# MotorShieldTestbench_ro.net
KiCad netlist of a schematic drawn in EAGLE
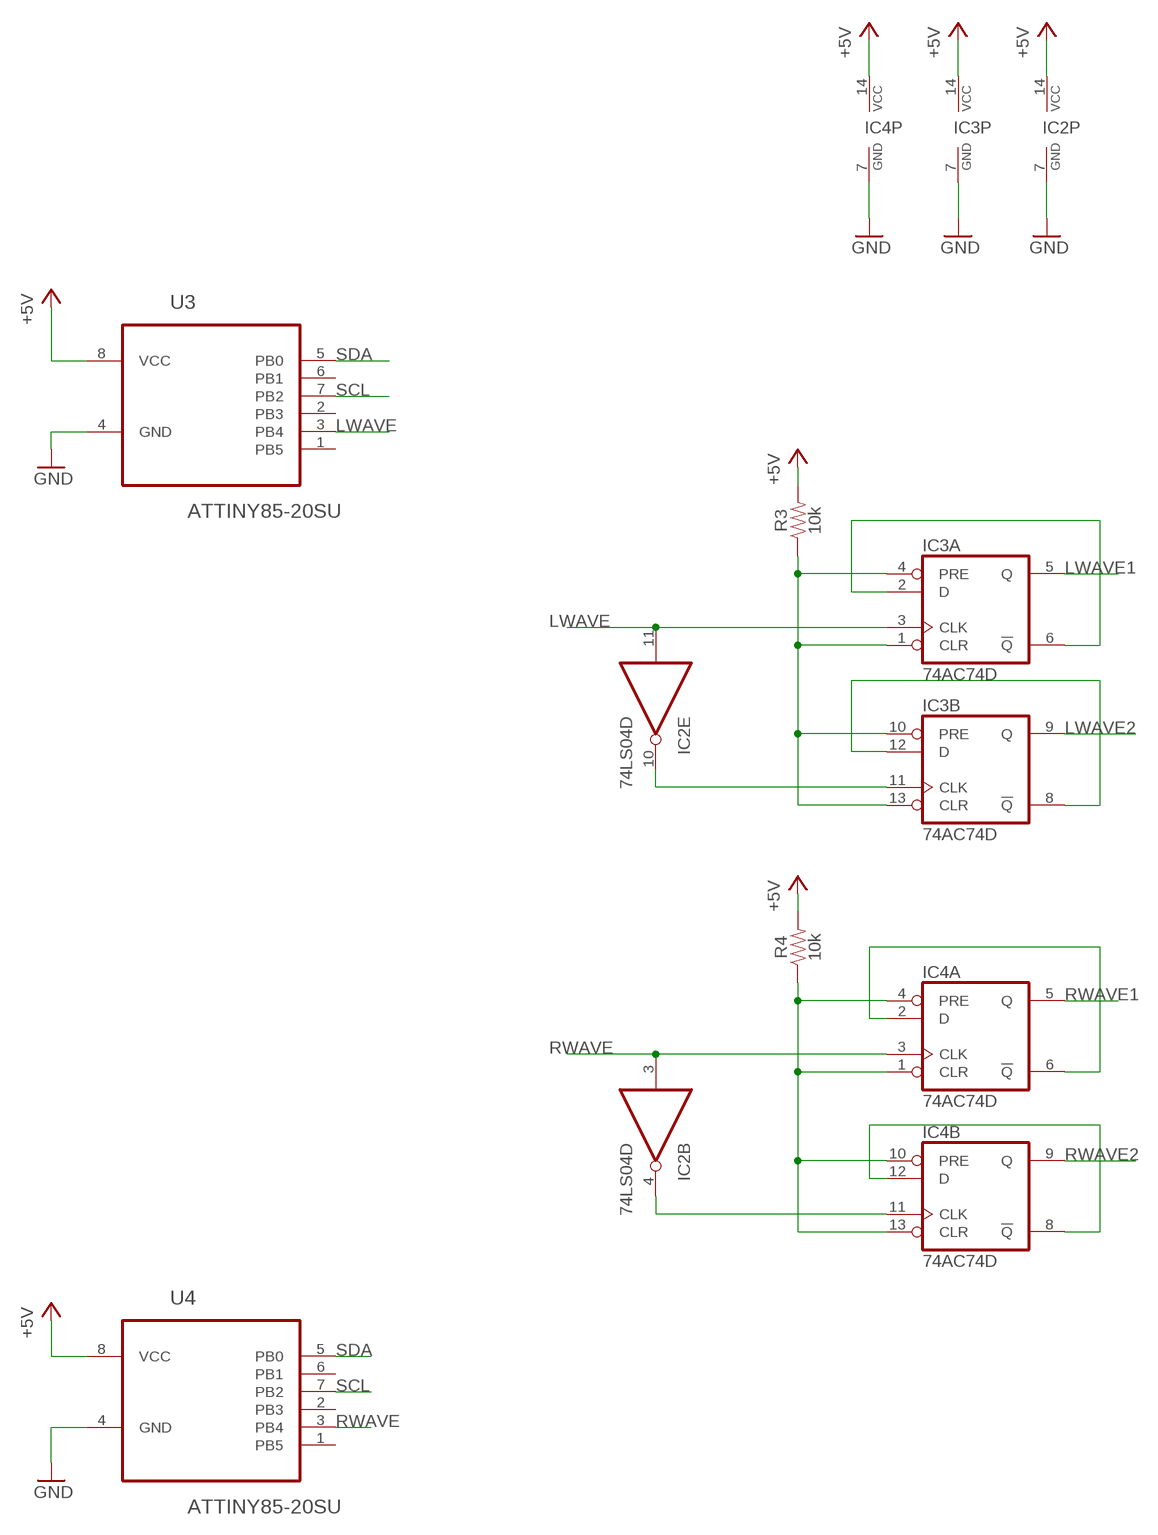
[diagram p0: schematic, sheet 1, part 1 of 2]
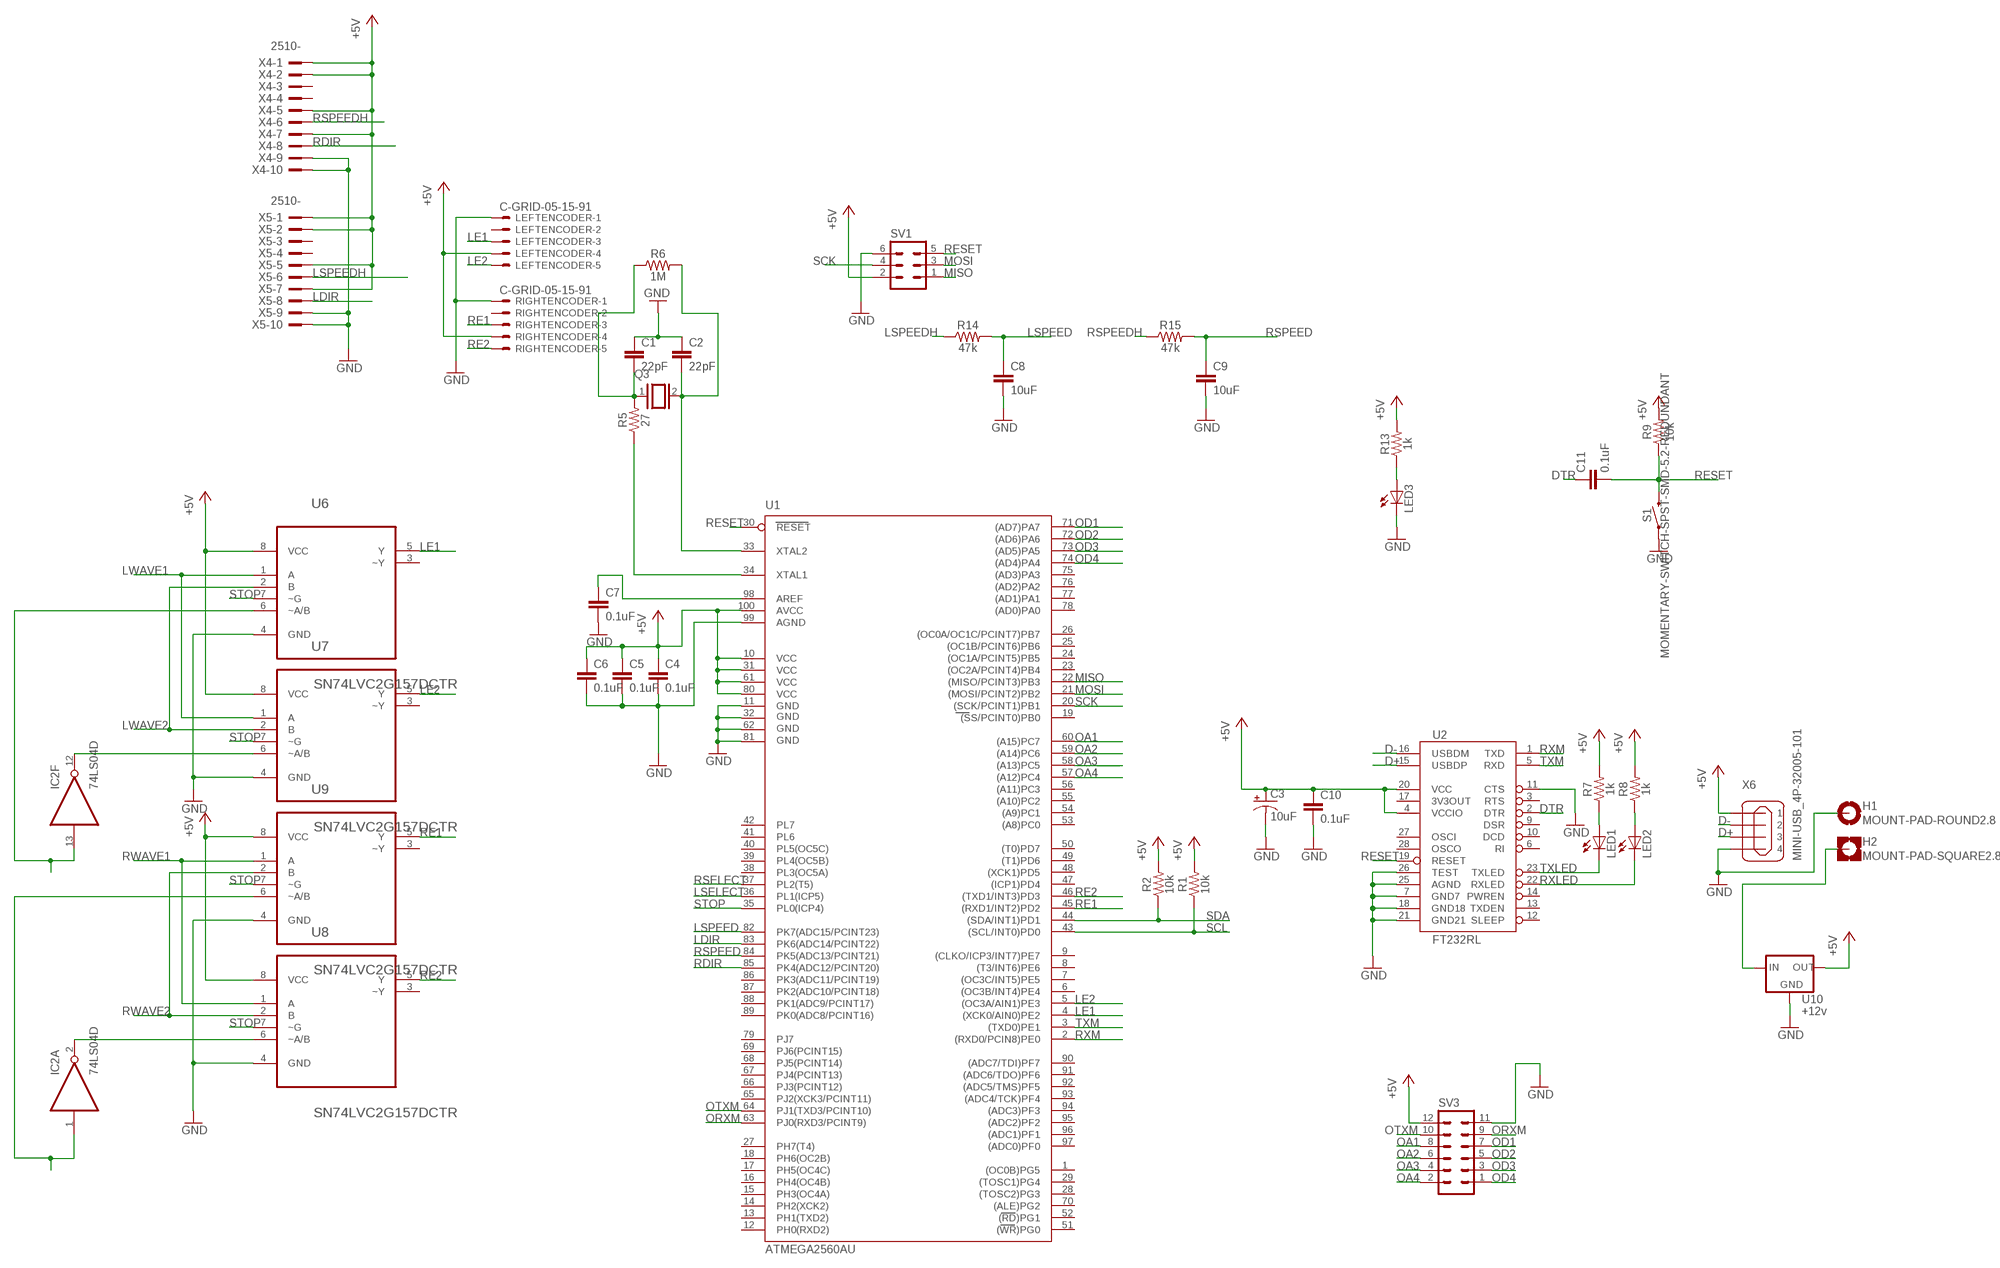
[diagram p1: schematic, sheet 1, part 2 of 2]

(export (version "E")
  (design (tool "Eeschema 10.0.6"))
  (components
    (comp (ref "C1")
      (value "22pF")
      (footprint "eagle-import:0603")
      (libsource (lib "eagle-import") (part "22PF-0603-50V-5%"))
    )
    (comp (ref "C2")
      (value "22pF")
      (footprint "eagle-import:0603")
      (libsource (lib "eagle-import") (part "22PF-0603-50V-5%"))
    )
    (comp (ref "C3")
      (value "10uF")
      (footprint "eagle-import:0603-POLAR")
      (libsource (lib "eagle-import") (part "10UF-POLAR-0603-6.3V-20%(TANT)"))
    )
    (comp (ref "C4")
      (value "0.1uF")
      (footprint "eagle-import:0603")
      (libsource (lib "eagle-import") (part "0.1UF-0603-25V-(+80/-20%)"))
    )
    (comp (ref "C5")
      (value "0.1uF")
      (footprint "eagle-import:0603")
      (libsource (lib "eagle-import") (part "0.1UF-0603-25V-(+80/-20%)"))
    )
    (comp (ref "C6")
      (value "0.1uF")
      (footprint "eagle-import:0603")
      (libsource (lib "eagle-import") (part "0.1UF-0603-25V-(+80/-20%)"))
    )
    (comp (ref "C7")
      (value "0.1uF")
      (footprint "eagle-import:0603")
      (libsource (lib "eagle-import") (part "0.1UF-0603-25V-(+80/-20%)"))
    )
    (comp (ref "C8")
      (value "10uF")
      (footprint "eagle-import:0603")
      (libsource (lib "eagle-import") (part "10UF-0603-6.3V-20%"))
    )
    (comp (ref "C9")
      (value "10uF")
      (footprint "eagle-import:0603")
      (libsource (lib "eagle-import") (part "10UF-0603-6.3V-20%"))
    )
    (comp (ref "C10")
      (value "0.1uF")
      (footprint "eagle-import:0402")
      (libsource (lib "eagle-import") (part "0.1UF-0402-16V-10%"))
    )
    (comp (ref "C11")
      (value "0.1uF")
      (footprint "eagle-import:0603")
      (libsource (lib "eagle-import") (part "0.1UF-0603-25V-(+80/-20%)"))
    )
    (comp (ref "H1")
      (value "MOUNT-PAD-ROUND2.8")
      (footprint "eagle-import:2,8-PAD")
      (libsource (lib "eagle-import") (part "MOUNT-PAD-ROUND2.8"))
    )
    (comp (ref "H2")
      (value "MOUNT-PAD-SQUARE2.8")
      (footprint "eagle-import:2,8-PAD-SQUARE")
      (libsource (lib "eagle-import") (part "MOUNT-PAD-SQUARE2.8"))
    )
    (comp (ref "IC2")
      (value "74LS04D")
      (footprint "eagle-import:SO14")
      (libsource (lib "eagle-import") (part "7404DLS"))
    )
    (comp (ref "IC3")
      (value "74AC74D")
      (footprint "eagle-import:SO14")
      (libsource (lib "eagle-import") (part "7474DAC"))
    )
    (comp (ref "IC4")
      (value "74AC74D")
      (footprint "eagle-import:SO14")
      (libsource (lib "eagle-import") (part "7474DAC"))
    )
    (comp (ref "LED1")
      (value "LED_E")
      (footprint "eagle-import:LED_1206")
      (libsource (lib "eagle-import") (part "LED_E"))
    )
    (comp (ref "LED2")
      (value "LED_E")
      (footprint "eagle-import:LED_1206")
      (libsource (lib "eagle-import") (part "LED_E"))
    )
    (comp (ref "LED3")
      (value "LED_E")
      (footprint "eagle-import:LED_1206")
      (libsource (lib "eagle-import") (part "LED_E"))
    )
    (comp (ref "LEFTENCODER")
      (value "C-GRID-05-15-91")
      (footprint "eagle-import:15-91-05")
      (libsource (lib "eagle-import") (part "C-GRID-05-15-91"))
    )
    (comp (ref "Q3")
      (value "XTAL/S")
      (footprint "eagle-import:QS")
      (libsource (lib "eagle-import") (part "XTAL/S"))
    )
    (comp (ref "R1")
      (value "10k")
      (footprint "eagle-import:0603")
      (libsource (lib "eagle-import") (part "10KOHM-0603-1/10W-1%"))
    )
    (comp (ref "R2")
      (value "10k")
      (footprint "eagle-import:0603")
      (libsource (lib "eagle-import") (part "10KOHM-0603-1/10W-1%"))
    )
    (comp (ref "R3")
      (value "10k")
      (footprint "eagle-import:0603")
      (libsource (lib "eagle-import") (part "10KOHM-0603-1/10W-1%"))
    )
    (comp (ref "R4")
      (value "10k")
      (footprint "eagle-import:0603")
      (libsource (lib "eagle-import") (part "10KOHM-0603-1/10W-1%"))
    )
    (comp (ref "R5")
      (value "27")
      (footprint "eagle-import:0603")
      (libsource (lib "eagle-import") (part "27OHM-0603-1/10W-1%"))
    )
    (comp (ref "R6")
      (value "1M")
      (footprint "eagle-import:0603")
      (libsource (lib "eagle-import") (part "1MOHM-0603-1/4W-5%"))
    )
    (comp (ref "R7")
      (value "1k")
      (footprint "eagle-import:0603")
      (libsource (lib "eagle-import") (part "1KOHM-0603-1/10W-1%"))
    )
    (comp (ref "R8")
      (value "1k")
      (footprint "eagle-import:0603")
      (libsource (lib "eagle-import") (part "1KOHM-0603-1/10W-1%"))
    )
    (comp (ref "R9")
      (value "10k")
      (footprint "eagle-import:0603")
      (libsource (lib "eagle-import") (part "10KOHM-0603-1/10W-1%"))
    )
    (comp (ref "R13")
      (value "1k")
      (footprint "eagle-import:0603")
      (libsource (lib "eagle-import") (part "1KOHM-0603-1/10W-1%"))
    )
    (comp (ref "R14")
      (value "47k")
      (footprint "eagle-import:0603")
      (libsource (lib "eagle-import") (part "47KOHM-0603-1/10W-1%"))
    )
    (comp (ref "R15")
      (value "47k")
      (footprint "eagle-import:0603")
      (libsource (lib "eagle-import") (part "47KOHM-0603-1/10W-1%"))
    )
    (comp (ref "RIGHTENCODER")
      (value "C-GRID-05-15-91")
      (footprint "eagle-import:15-91-05")
      (libsource (lib "eagle-import") (part "C-GRID-05-15-91"))
    )
    (comp (ref "S1")
      (value "MOMENTARY-SWITCH-SPST-SMD-5.2-REDUNDANT")
      (footprint "eagle-import:TACTILE_SWITCH_SMD_5.2MM")
      (libsource (lib "eagle-import") (part "MOMENTARY-SWITCH-SPST-SMD-5.2-REDUNDANT"))
    )
    (comp (ref "SV1")
      (value "MA03-2")
      (footprint "eagle-import:MA03-2")
      (libsource (lib "eagle-import") (part "MA03-2"))
    )
    (comp (ref "SV3")
      (value "MA06-2")
      (footprint "eagle-import:MA06-2")
      (libsource (lib "eagle-import") (part "MA06-2"))
    )
    (comp (ref "U1")
      (value "ATMEGA2560AU")
      (footprint "eagle-import:TQFP100")
      (libsource (lib "eagle-import") (part "ATMEGA2560AU"))
    )
    (comp (ref "U2")
      (value "FT232RL")
      (footprint "eagle-import:SSOP28DB")
      (libsource (lib "eagle-import") (part "FT232RLSSOP"))
    )
    (comp (ref "U3")
      (value "ATTINY85-20SU")
      (footprint "eagle-import:SOIC127P798X216-8N")
      (libsource (lib "eagle-import") (part "ATTINY85-20SU"))
    )
    (comp (ref "U4")
      (value "ATTINY85-20SU")
      (footprint "eagle-import:SOIC127P798X216-8N")
      (libsource (lib "eagle-import") (part "ATTINY85-20SU"))
    )
    (comp (ref "U6")
      (value "SN74LVC2G157DCTR")
      (footprint "eagle-import:SOP65P400X130-8N")
      (libsource (lib "eagle-import") (part "SN74LVC2G157DCTR"))
    )
    (comp (ref "U7")
      (value "SN74LVC2G157DCTR")
      (footprint "eagle-import:SOP65P400X130-8N")
      (libsource (lib "eagle-import") (part "SN74LVC2G157DCTR"))
    )
    (comp (ref "U8")
      (value "SN74LVC2G157DCTR")
      (footprint "eagle-import:SOP65P400X130-8N")
      (libsource (lib "eagle-import") (part "SN74LVC2G157DCTR"))
    )
    (comp (ref "U9")
      (value "SN74LVC2G157DCTR")
      (footprint "eagle-import:SOP65P400X130-8N")
      (libsource (lib "eagle-import") (part "SN74LVC2G157DCTR"))
    )
    (comp (ref "U10")
      (value "+12v")
      (footprint "eagle-import:TO-252")
      (libsource (lib "eagle-import") (part "V_REG_78XX7812"))
    )
    (comp (ref "X4")
      (value "2510-")
      (footprint "eagle-import:PAK100_2500-10")
      (fields (field (name "MF") "3M") (field (name "MPN") "2510-6002UB"))
      (libsource (lib "eagle-import") (part "2510-"))
    )
    (comp (ref "X5")
      (value "2510-")
      (footprint "eagle-import:PAK100_2500-10")
      (fields (field (name "MF") "3M") (field (name "MPN") "2510-6002UB"))
      (libsource (lib "eagle-import") (part "2510-"))
    )
    (comp (ref "X6")
      (value "MINI-USB_4P-32005-101")
      (footprint "eagle-import:32005-101")
      (libsource (lib "eagle-import") (part "MINI-USB_4P-32005-101"))
    )
  )
  (nets
    (net (code "1") (name "+5V") (class "Default")
      (node (ref "C10") (pin "1") (pinfunction "1_1") (pintype "passive"))
      (node (ref "C3") (pin "+") (pinfunction "+_+") (pintype "passive"))
      (node (ref "C4") (pin "1") (pinfunction "1_1") (pintype "passive"))
      (node (ref "C5") (pin "1") (pinfunction "1_1") (pintype "passive"))
      (node (ref "C6") (pin "1") (pinfunction "1_1") (pintype "passive"))
      (node (ref "IC2") (pin "14") (pinfunction "VCC_14") (pintype "power_in"))
      (node (ref "IC3") (pin "14") (pinfunction "VCC_14") (pintype "power_in"))
      (node (ref "IC4") (pin "14") (pinfunction "VCC_14") (pintype "power_in"))
      (node (ref "LEFTENCODER") (pin "4") (pinfunction "S_4") (pintype "passive"))
      (node (ref "R1") (pin "2") (pinfunction "2_2") (pintype "passive"))
      (node (ref "R13") (pin "2") (pinfunction "2_2") (pintype "passive"))
      (node (ref "R2") (pin "2") (pinfunction "2_2") (pintype "passive"))
      (node (ref "R3") (pin "2") (pinfunction "2_2") (pintype "passive"))
      (node (ref "R4") (pin "2") (pinfunction "2_2") (pintype "passive"))
      (node (ref "R7") (pin "2") (pinfunction "2_2") (pintype "passive"))
      (node (ref "R8") (pin "2") (pinfunction "2_2") (pintype "passive"))
      (node (ref "R9") (pin "2") (pinfunction "2_2") (pintype "passive"))
      (node (ref "RIGHTENCODER") (pin "4") (pinfunction "S_4") (pintype "passive"))
      (node (ref "SV1") (pin "2") (pinfunction "2_2") (pintype "passive"))
      (node (ref "SV3") (pin "12") (pinfunction "12_12") (pintype "passive"))
      (node (ref "U1") (pin "10") (pinfunction "VCC_10") (pintype "power_in"))
      (node (ref "U1") (pin "100") (pinfunction "AVCC_100") (pintype "power_in"))
      (node (ref "U1") (pin "31") (pinfunction "VCC1_31") (pintype "power_in"))
      (node (ref "U1") (pin "61") (pinfunction "VCC2_61") (pintype "power_in"))
      (node (ref "U1") (pin "80") (pinfunction "VCC3_80") (pintype "power_in"))
      (node (ref "U10") (pin "2") (pinfunction "OUT_2") (pintype "passive"))
      (node (ref "U2") (pin "20") (pinfunction "VCC_20") (pintype "power_in"))
      (node (ref "U2") (pin "4") (pinfunction "VCCIO_4") (pintype "power_in"))
      (node (ref "U3") (pin "8") (pinfunction "VCC_8") (pintype "power_in"))
      (node (ref "U4") (pin "8") (pinfunction "VCC_8") (pintype "power_in"))
      (node (ref "U6") (pin "8") (pinfunction "VCC_8") (pintype "power_in"))
      (node (ref "U7") (pin "8") (pinfunction "VCC_8") (pintype "power_in"))
      (node (ref "U8") (pin "8") (pinfunction "VCC_8") (pintype "power_in"))
      (node (ref "U9") (pin "8") (pinfunction "VCC_8") (pintype "power_in"))
      (node (ref "X4") (pin "1") (pinfunction "KL_1") (pintype "passive"))
      (node (ref "X4") (pin "2") (pinfunction "KL_2") (pintype "passive"))
      (node (ref "X4") (pin "5") (pinfunction "KL_5") (pintype "passive"))
      (node (ref "X4") (pin "7") (pinfunction "KL_7") (pintype "passive"))
      (node (ref "X5") (pin "1") (pinfunction "KL_1") (pintype "passive"))
      (node (ref "X5") (pin "2") (pinfunction "KL_2") (pintype "passive"))
      (node (ref "X5") (pin "5") (pinfunction "KL_5") (pintype "passive"))
      (node (ref "X5") (pin "7") (pinfunction "KL_7") (pintype "passive"))
      (node (ref "X6") (pin "1") (pinfunction "1_1") (pintype "passive"))
    )
    (net (code "2") (name "/D+") (class "Default")
      (node (ref "U2") (pin "15") (pinfunction "USBDP_15") (pintype "bidirectional"))
      (node (ref "X6") (pin "3") (pinfunction "3_3") (pintype "passive"))
    )
    (net (code "3") (name "/D-") (class "Default")
      (node (ref "U2") (pin "16") (pinfunction "USBDM_16") (pintype "bidirectional"))
      (node (ref "X6") (pin "2") (pinfunction "2_2") (pintype "passive"))
    )
    (net (code "4") (name "/DTR") (class "Default")
      (node (ref "C11") (pin "1") (pinfunction "1_1") (pintype "passive"))
      (node (ref "U2") (pin "2") (pinfunction "DTR_2") (pintype "output"))
    )
    (net (code "5") (name "/LDIR") (class "Default")
      (node (ref "U1") (pin "83") (pinfunction "PK6(ADC14/PCINT22)_83") (pintype "bidirectional"))
      (node (ref "X5") (pin "8") (pinfunction "KL_8") (pintype "passive"))
    )
    (net (code "6") (name "/LE1") (class "Default")
      (node (ref "LEFTENCODER") (pin "3") (pinfunction "S_3") (pintype "passive"))
      (node (ref "U1") (pin "4") (pinfunction "(XCK0/AIN0)PE2_4") (pintype "bidirectional"))
      (node (ref "U6") (pin "5") (pinfunction "Y_5") (pintype "output"))
    )
    (net (code "7") (name "/LE2") (class "Default")
      (node (ref "LEFTENCODER") (pin "5") (pinfunction "S_5") (pintype "passive"))
      (node (ref "U1") (pin "5") (pinfunction "(OC3A/AIN1)PE3_5") (pintype "bidirectional"))
      (node (ref "U7") (pin "5") (pinfunction "Y_5") (pintype "output"))
    )
    (net (code "8") (name "/LSELECT") (class "Default")
      (node (ref "IC2") (pin "13") (pinfunction "I_13") (pintype "input"))
      (node (ref "U1") (pin "36") (pinfunction "PL1(ICP5)_36") (pintype "bidirectional"))
      (node (ref "U6") (pin "6") (pinfunction "~{A/B}_6") (pintype "input"))
    )
    (net (code "9") (name "/LSPEED") (class "Default")
      (node (ref "C8") (pin "1") (pinfunction "1_1") (pintype "passive"))
      (node (ref "R14") (pin "2") (pinfunction "2_2") (pintype "passive"))
      (node (ref "U1") (pin "82") (pinfunction "PK7(ADC15/PCINT23)_82") (pintype "bidirectional"))
    )
    (net (code "10") (name "/LSPEEDH") (class "Default")
      (node (ref "R14") (pin "1") (pinfunction "1_1") (pintype "passive"))
      (node (ref "X5") (pin "6") (pinfunction "KL_6") (pintype "passive"))
    )
    (net (code "11") (name "/LWAVE") (class "Default")
      (node (ref "IC2") (pin "11") (pinfunction "I_11") (pintype "input"))
      (node (ref "IC3") (pin "3") (pinfunction "CLK_3") (pintype "input"))
      (node (ref "U3") (pin "3") (pinfunction "PB4_3") (pintype "bidirectional"))
    )
    (net (code "12") (name "/LWAVE1") (class "Default")
      (node (ref "IC3") (pin "5") (pinfunction "Q_5") (pintype "output"))
      (node (ref "U6") (pin "1") (pinfunction "A_1") (pintype "input"))
      (node (ref "U7") (pin "1") (pinfunction "A_1") (pintype "input"))
    )
    (net (code "13") (name "/LWAVE2") (class "Default")
      (node (ref "IC3") (pin "9") (pinfunction "Q_9") (pintype "output"))
      (node (ref "U6") (pin "2") (pinfunction "B_2") (pintype "input"))
      (node (ref "U7") (pin "2") (pinfunction "B_2") (pintype "input"))
    )
    (net (code "14") (name "/MISO") (class "Default")
      (node (ref "SV1") (pin "1") (pinfunction "1_1") (pintype "passive"))
      (node (ref "U1") (pin "22") (pinfunction "(MISO/PCINT3)PB3_22") (pintype "bidirectional"))
    )
    (net (code "15") (name "/MOSI") (class "Default")
      (node (ref "SV1") (pin "3") (pinfunction "3_3") (pintype "passive"))
      (node (ref "U1") (pin "21") (pinfunction "(MOSI/PCINT2)PB2_21") (pintype "bidirectional"))
    )
    (net (code "16") (name "/OA1") (class "Default")
      (node (ref "SV3") (pin "8") (pinfunction "8_8") (pintype "passive"))
      (node (ref "U1") (pin "60") (pinfunction "(A15)PC7_60") (pintype "bidirectional"))
    )
    (net (code "17") (name "/OA2") (class "Default")
      (node (ref "SV3") (pin "6") (pinfunction "6_6") (pintype "passive"))
      (node (ref "U1") (pin "59") (pinfunction "(A14)PC6_59") (pintype "bidirectional"))
    )
    (net (code "18") (name "/OA3") (class "Default")
      (node (ref "SV3") (pin "4") (pinfunction "4_4") (pintype "passive"))
      (node (ref "U1") (pin "58") (pinfunction "(A13)PC5_58") (pintype "bidirectional"))
    )
    (net (code "19") (name "/OA4") (class "Default")
      (node (ref "SV3") (pin "2") (pinfunction "2_2") (pintype "passive"))
      (node (ref "U1") (pin "57") (pinfunction "(A12)PC4_57") (pintype "bidirectional"))
    )
    (net (code "20") (name "/OD1") (class "Default")
      (node (ref "SV3") (pin "7") (pinfunction "7_7") (pintype "passive"))
      (node (ref "U1") (pin "71") (pinfunction "(AD7)PA7_71") (pintype "bidirectional"))
    )
    (net (code "21") (name "/OD2") (class "Default")
      (node (ref "SV3") (pin "5") (pinfunction "5_5") (pintype "passive"))
      (node (ref "U1") (pin "72") (pinfunction "(AD6)PA6_72") (pintype "bidirectional"))
    )
    (net (code "22") (name "/OD3") (class "Default")
      (node (ref "SV3") (pin "3") (pinfunction "3_3") (pintype "passive"))
      (node (ref "U1") (pin "73") (pinfunction "(AD5)PA5_73") (pintype "bidirectional"))
    )
    (net (code "23") (name "/OD4") (class "Default")
      (node (ref "SV3") (pin "1") (pinfunction "1_1") (pintype "passive"))
      (node (ref "U1") (pin "74") (pinfunction "(AD4)PA4_74") (pintype "bidirectional"))
    )
    (net (code "24") (name "/ORXM") (class "Default")
      (node (ref "SV3") (pin "9") (pinfunction "9_9") (pintype "passive"))
      (node (ref "U1") (pin "63") (pinfunction "PJ0(RXD3/PCINT9)_63") (pintype "bidirectional"))
    )
    (net (code "25") (name "/OTXM") (class "Default")
      (node (ref "SV3") (pin "10") (pinfunction "10_10") (pintype "passive"))
      (node (ref "U1") (pin "64") (pinfunction "PJ1(TXD3/PCINT10)_64") (pintype "bidirectional"))
    )
    (net (code "26") (name "/RDIR") (class "Default")
      (node (ref "U1") (pin "85") (pinfunction "PK4(ADC12/PCINT20)_85") (pintype "bidirectional"))
      (node (ref "X4") (pin "8") (pinfunction "KL_8") (pintype "passive"))
    )
    (net (code "27") (name "/RE1") (class "Default")
      (node (ref "RIGHTENCODER") (pin "3") (pinfunction "S_3") (pintype "passive"))
      (node (ref "U1") (pin "45") (pinfunction "(RXD1/INT2)PD2_45") (pintype "bidirectional"))
      (node (ref "U9") (pin "5") (pinfunction "Y_5") (pintype "output"))
    )
    (net (code "28") (name "/RE2") (class "Default")
      (node (ref "RIGHTENCODER") (pin "5") (pinfunction "S_5") (pintype "passive"))
      (node (ref "U1") (pin "46") (pinfunction "(TXD1/INT3)PD3_46") (pintype "bidirectional"))
      (node (ref "U8") (pin "5") (pinfunction "Y_5") (pintype "output"))
    )
    (net (code "29") (name "/RESET") (class "Default")
      (node (ref "C11") (pin "2") (pinfunction "2_2") (pintype "passive"))
      (node (ref "R9") (pin "1") (pinfunction "1_1") (pintype "passive"))
      (node (ref "S1") (pin "3") (pinfunction "2_3") (pintype "passive"))
      (node (ref "S1") (pin "4") (pinfunction "2_4") (pintype "passive"))
      (node (ref "SV1") (pin "5") (pinfunction "5_5") (pintype "passive"))
      (node (ref "U1") (pin "30") (pinfunction "RESET_30") (pintype "input"))
      (node (ref "U2") (pin "19") (pinfunction "RESET_19") (pintype "input"))
    )
    (net (code "30") (name "/RSELECT") (class "Default")
      (node (ref "IC2") (pin "1") (pinfunction "I_1") (pintype "input"))
      (node (ref "U1") (pin "37") (pinfunction "PL2(T5)_37") (pintype "bidirectional"))
      (node (ref "U9") (pin "6") (pinfunction "~{A/B}_6") (pintype "input"))
    )
    (net (code "31") (name "/RSPEED") (class "Default")
      (node (ref "C9") (pin "1") (pinfunction "1_1") (pintype "passive"))
      (node (ref "R15") (pin "2") (pinfunction "2_2") (pintype "passive"))
      (node (ref "U1") (pin "84") (pinfunction "PK5(ADC13/PCINT21)_84") (pintype "bidirectional"))
    )
    (net (code "32") (name "/RSPEEDH") (class "Default")
      (node (ref "R15") (pin "1") (pinfunction "1_1") (pintype "passive"))
      (node (ref "X4") (pin "6") (pinfunction "KL_6") (pintype "passive"))
    )
    (net (code "33") (name "/RWAVE") (class "Default")
      (node (ref "IC2") (pin "3") (pinfunction "I_3") (pintype "input"))
      (node (ref "IC4") (pin "3") (pinfunction "CLK_3") (pintype "input"))
      (node (ref "U4") (pin "3") (pinfunction "PB4_3") (pintype "bidirectional"))
    )
    (net (code "34") (name "/RWAVE1") (class "Default")
      (node (ref "IC4") (pin "5") (pinfunction "Q_5") (pintype "output"))
      (node (ref "U8") (pin "1") (pinfunction "A_1") (pintype "input"))
      (node (ref "U9") (pin "1") (pinfunction "A_1") (pintype "input"))
    )
    (net (code "35") (name "/RWAVE2") (class "Default")
      (node (ref "IC4") (pin "9") (pinfunction "Q_9") (pintype "output"))
      (node (ref "U8") (pin "2") (pinfunction "B_2") (pintype "input"))
      (node (ref "U9") (pin "2") (pinfunction "B_2") (pintype "input"))
    )
    (net (code "36") (name "/RXLED") (class "Default")
      (node (ref "LED2") (pin "C") (pinfunction "C_C") (pintype "passive"))
      (node (ref "U2") (pin "22") (pinfunction "RXLED_22") (pintype "input"))
    )
    (net (code "37") (name "/RXM") (class "Default")
      (node (ref "U1") (pin "2") (pinfunction "(RXD0/PCIN8)PE0_2") (pintype "bidirectional"))
      (node (ref "U2") (pin "1") (pinfunction "TXD_1") (pintype "output"))
    )
    (net (code "38") (name "/SCK") (class "Default")
      (node (ref "SV1") (pin "4") (pinfunction "4_4") (pintype "passive"))
      (node (ref "U1") (pin "20") (pinfunction "(SCK/PCINT1)PB1_20") (pintype "bidirectional"))
    )
    (net (code "39") (name "/SCL") (class "Default")
      (node (ref "R1") (pin "1") (pinfunction "1_1") (pintype "passive"))
      (node (ref "U1") (pin "43") (pinfunction "(SCL/INT0)PD0_43") (pintype "bidirectional"))
      (node (ref "U3") (pin "7") (pinfunction "PB2_7") (pintype "bidirectional"))
      (node (ref "U4") (pin "7") (pinfunction "PB2_7") (pintype "bidirectional"))
    )
    (net (code "40") (name "/SDA") (class "Default")
      (node (ref "R2") (pin "1") (pinfunction "1_1") (pintype "passive"))
      (node (ref "U1") (pin "44") (pinfunction "(SDA/INT1)PD1_44") (pintype "bidirectional"))
      (node (ref "U3") (pin "5") (pinfunction "PB0_5") (pintype "bidirectional"))
      (node (ref "U4") (pin "5") (pinfunction "PB0_5") (pintype "bidirectional"))
    )
    (net (code "41") (name "/STOP") (class "Default")
      (node (ref "U1") (pin "35") (pinfunction "PL0(ICP4)_35") (pintype "bidirectional"))
      (node (ref "U6") (pin "7") (pinfunction "~{G}_7") (pintype "input"))
      (node (ref "U7") (pin "7") (pinfunction "~{G}_7") (pintype "input"))
      (node (ref "U8") (pin "7") (pinfunction "~{G}_7") (pintype "input"))
      (node (ref "U9") (pin "7") (pinfunction "~{G}_7") (pintype "input"))
    )
    (net (code "42") (name "/TXLED") (class "Default")
      (node (ref "LED1") (pin "C") (pinfunction "C_C") (pintype "passive"))
      (node (ref "U2") (pin "23") (pinfunction "TXLED_23") (pintype "input"))
    )
    (net (code "43") (name "/TXM") (class "Default")
      (node (ref "U1") (pin "3") (pinfunction "(TXD0)PE1_3") (pintype "bidirectional"))
      (node (ref "U2") (pin "5") (pinfunction "RXD_5") (pintype "input"))
    )
    (net (code "44") (name "GND") (class "Default")
      (node (ref "C1") (pin "1") (pinfunction "1_1") (pintype "passive"))
      (node (ref "C10") (pin "2") (pinfunction "2_2") (pintype "passive"))
      (node (ref "C2") (pin "1") (pinfunction "1_1") (pintype "passive"))
      (node (ref "C3") (pin "-") (pinfunction "-_-") (pintype "passive"))
      (node (ref "C4") (pin "2") (pinfunction "2_2") (pintype "passive"))
      (node (ref "C5") (pin "2") (pinfunction "2_2") (pintype "passive"))
      (node (ref "C6") (pin "2") (pinfunction "2_2") (pintype "passive"))
      (node (ref "C7") (pin "2") (pinfunction "2_2") (pintype "passive"))
      (node (ref "C8") (pin "2") (pinfunction "2_2") (pintype "passive"))
      (node (ref "C9") (pin "2") (pinfunction "2_2") (pintype "passive"))
      (node (ref "H1") (pin "B2,8") (pinfunction "MOUNT_B2,8") (pintype "passive"))
      (node (ref "IC2") (pin "7") (pinfunction "GND_7") (pintype "power_in"))
      (node (ref "IC3") (pin "7") (pinfunction "GND_7") (pintype "power_in"))
      (node (ref "IC4") (pin "7") (pinfunction "GND_7") (pintype "power_in"))
      (node (ref "LED3") (pin "C") (pinfunction "C_C") (pintype "passive"))
      (node (ref "LEFTENCODER") (pin "1") (pinfunction "S_1") (pintype "passive"))
      (node (ref "RIGHTENCODER") (pin "1") (pinfunction "S_1") (pintype "passive"))
      (node (ref "S1") (pin "1") (pinfunction "1_1") (pintype "passive"))
      (node (ref "S1") (pin "2") (pinfunction "1_2") (pintype "passive"))
      (node (ref "SV1") (pin "6") (pinfunction "6_6") (pintype "passive"))
      (node (ref "SV3") (pin "11") (pinfunction "11_11") (pintype "passive"))
      (node (ref "U1") (pin "11") (pinfunction "GND_11") (pintype "power_in"))
      (node (ref "U1") (pin "32") (pinfunction "GND1_32") (pintype "power_in"))
      (node (ref "U1") (pin "62") (pinfunction "GND2_62") (pintype "power_in"))
      (node (ref "U1") (pin "81") (pinfunction "GND3_81") (pintype "power_in"))
      (node (ref "U1") (pin "99") (pinfunction "AGND_99") (pintype "power_in"))
      (node (ref "U10") (pin "3") (pinfunction "GND_3") (pintype "input"))
      (node (ref "U2") (pin "11") (pinfunction "CTS_11") (pintype "input"))
      (node (ref "U2") (pin "18") (pinfunction "GND18_18") (pintype "power_in"))
      (node (ref "U2") (pin "21") (pinfunction "GND21_21") (pintype "power_in"))
      (node (ref "U2") (pin "25") (pinfunction "AGND_25") (pintype "power_in"))
      (node (ref "U2") (pin "26") (pinfunction "TEST_26") (pintype "input"))
      (node (ref "U2") (pin "7") (pinfunction "GND7_7") (pintype "power_in"))
      (node (ref "U3") (pin "4") (pinfunction "GND_4") (pintype "passive"))
      (node (ref "U4") (pin "4") (pinfunction "GND_4") (pintype "passive"))
      (node (ref "U6") (pin "4") (pinfunction "GND_4") (pintype "passive"))
      (node (ref "U7") (pin "4") (pinfunction "GND_4") (pintype "passive"))
      (node (ref "U8") (pin "4") (pinfunction "GND_4") (pintype "passive"))
      (node (ref "U9") (pin "4") (pinfunction "GND_4") (pintype "passive"))
      (node (ref "X4") (pin "10") (pinfunction "KL_10") (pintype "passive"))
      (node (ref "X4") (pin "9") (pinfunction "KL_9") (pintype "passive"))
      (node (ref "X5") (pin "10") (pinfunction "KL_10") (pintype "passive"))
      (node (ref "X5") (pin "9") (pinfunction "KL_9") (pintype "passive"))
      (node (ref "X6") (pin "4") (pinfunction "4_4") (pintype "passive"))
    )
    (net (code "45") (name "Net-(C1-Pad2)") (class "Default")
      (node (ref "C1") (pin "2") (pinfunction "2_2") (pintype "passive"))
      (node (ref "Q3") (pin "1") (pinfunction "1_1") (pintype "passive"))
      (node (ref "R5") (pin "2") (pinfunction "2_2") (pintype "passive"))
      (node (ref "R6") (pin "1") (pinfunction "1_1") (pintype "passive"))
    )
    (net (code "46") (name "Net-(H2-MOUNT)") (class "Default")
      (node (ref "H2") (pin "B2,8") (pinfunction "MOUNT_B2,8") (pintype "passive"))
      (node (ref "U10") (pin "1") (pinfunction "IN_1") (pintype "input"))
    )
    (net (code "47") (name "Net-(IC2A-O)") (class "Default")
      (node (ref "IC2") (pin "2") (pinfunction "O_2") (pintype "output"))
      (node (ref "U8") (pin "6") (pinfunction "~{A/B}_6") (pintype "input"))
    )
    (net (code "48") (name "Net-(IC2B-O)") (class "Default")
      (node (ref "IC2") (pin "4") (pinfunction "O_4") (pintype "output"))
      (node (ref "IC4") (pin "11") (pinfunction "CLK_11") (pintype "input"))
    )
    (net (code "49") (name "Net-(IC2E-O)") (class "Default")
      (node (ref "IC2") (pin "10") (pinfunction "O_10") (pintype "output"))
      (node (ref "IC3") (pin "11") (pinfunction "CLK_11") (pintype "input"))
    )
    (net (code "50") (name "Net-(IC2F-O)") (class "Default")
      (node (ref "IC2") (pin "12") (pinfunction "O_12") (pintype "output"))
      (node (ref "U7") (pin "6") (pinfunction "~{A/B}_6") (pintype "input"))
    )
    (net (code "51") (name "Net-(IC3A-CLR)") (class "Default")
      (node (ref "IC3") (pin "1") (pinfunction "CLR_1") (pintype "input"))
      (node (ref "IC3") (pin "10") (pinfunction "PRE_10") (pintype "input"))
      (node (ref "IC3") (pin "13") (pinfunction "CLR_13") (pintype "input"))
      (node (ref "IC3") (pin "4") (pinfunction "PRE_4") (pintype "input"))
      (node (ref "R3") (pin "1") (pinfunction "1_1") (pintype "passive"))
    )
    (net (code "52") (name "Net-(IC3A-D)") (class "Default")
      (node (ref "IC3") (pin "2") (pinfunction "D_2") (pintype "input"))
      (node (ref "IC3") (pin "6") (pinfunction "~{Q}_6") (pintype "output"))
    )
    (net (code "53") (name "Net-(IC3B-D)") (class "Default")
      (node (ref "IC3") (pin "12") (pinfunction "D_12") (pintype "input"))
      (node (ref "IC3") (pin "8") (pinfunction "~{Q}_8") (pintype "output"))
    )
    (net (code "54") (name "Net-(IC4A-CLR)") (class "Default")
      (node (ref "IC4") (pin "1") (pinfunction "CLR_1") (pintype "input"))
      (node (ref "IC4") (pin "10") (pinfunction "PRE_10") (pintype "input"))
      (node (ref "IC4") (pin "13") (pinfunction "CLR_13") (pintype "input"))
      (node (ref "IC4") (pin "4") (pinfunction "PRE_4") (pintype "input"))
      (node (ref "R4") (pin "1") (pinfunction "1_1") (pintype "passive"))
    )
    (net (code "55") (name "Net-(IC4A-D)") (class "Default")
      (node (ref "IC4") (pin "2") (pinfunction "D_2") (pintype "input"))
      (node (ref "IC4") (pin "6") (pinfunction "~{Q}_6") (pintype "output"))
    )
    (net (code "56") (name "Net-(IC4B-D)") (class "Default")
      (node (ref "IC4") (pin "12") (pinfunction "D_12") (pintype "input"))
      (node (ref "IC4") (pin "8") (pinfunction "~{Q}_8") (pintype "output"))
    )
    (net (code "57") (name "Net-(LED1-PadA)") (class "Default")
      (node (ref "LED1") (pin "A") (pinfunction "A_A") (pintype "passive"))
      (node (ref "R7") (pin "1") (pinfunction "1_1") (pintype "passive"))
    )
    (net (code "58") (name "Net-(LED2-PadA)") (class "Default")
      (node (ref "LED2") (pin "A") (pinfunction "A_A") (pintype "passive"))
      (node (ref "R8") (pin "1") (pinfunction "1_1") (pintype "passive"))
    )
    (net (code "59") (name "Net-(LED3-PadA)") (class "Default")
      (node (ref "LED3") (pin "A") (pinfunction "A_A") (pintype "passive"))
      (node (ref "R13") (pin "1") (pinfunction "1_1") (pintype "passive"))
    )
    (net (code "60") (name "Net-(U1-AREF)") (class "Default")
      (node (ref "C7") (pin "1") (pinfunction "1_1") (pintype "passive"))
      (node (ref "U1") (pin "98") (pinfunction "AREF_98") (pintype "bidirectional"))
    )
    (net (code "61") (name "Net-(U1-XTAL1)") (class "Default")
      (node (ref "R5") (pin "1") (pinfunction "1_1") (pintype "passive"))
      (node (ref "U1") (pin "34") (pinfunction "XTAL1_34") (pintype "input"))
    )
    (net (code "62") (name "Net-(U1-XTAL2)") (class "Default")
      (node (ref "C2") (pin "2") (pinfunction "2_2") (pintype "passive"))
      (node (ref "Q3") (pin "2") (pinfunction "2_2") (pintype "passive"))
      (node (ref "R6") (pin "2") (pinfunction "2_2") (pintype "passive"))
      (node (ref "U1") (pin "33") (pinfunction "XTAL2_33") (pintype "output"))
    )
    (net (code "63") (name "unconnected-(LEFTENCODERB-S-Pad2)") (class "Default")
      (node (ref "LEFTENCODER") (pin "2") (pinfunction "S_2") (pintype "passive"))
    )
    (net (code "64") (name "unconnected-(RIGHTENCODERB-S-Pad2)") (class "Default")
      (node (ref "RIGHTENCODER") (pin "2") (pinfunction "S_2") (pintype "passive"))
    )
    (net (code "65") (name "unconnected-(U1-(A8)PC0-Pad53)") (class "Default")
      (node (ref "U1") (pin "53") (pinfunction "(A8)PC0_53") (pintype "bidirectional"))
    )
    (net (code "66") (name "unconnected-(U1-(A9)PC1-Pad54)") (class "Default")
      (node (ref "U1") (pin "54") (pinfunction "(A9)PC1_54") (pintype "bidirectional"))
    )
    (net (code "67") (name "unconnected-(U1-(A10)PC2-Pad55)") (class "Default")
      (node (ref "U1") (pin "55") (pinfunction "(A10)PC2_55") (pintype "bidirectional"))
    )
    (net (code "68") (name "unconnected-(U1-(A11)PC3-Pad56)") (class "Default")
      (node (ref "U1") (pin "56") (pinfunction "(A11)PC3_56") (pintype "bidirectional"))
    )
    (net (code "69") (name "unconnected-(U1-(AD0)PA0-Pad78)") (class "Default")
      (node (ref "U1") (pin "78") (pinfunction "(AD0)PA0_78") (pintype "bidirectional"))
    )
    (net (code "70") (name "unconnected-(U1-(AD1)PA1-Pad77)") (class "Default")
      (node (ref "U1") (pin "77") (pinfunction "(AD1)PA1_77") (pintype "bidirectional"))
    )
    (net (code "71") (name "unconnected-(U1-(AD2)PA2-Pad76)") (class "Default")
      (node (ref "U1") (pin "76") (pinfunction "(AD2)PA2_76") (pintype "bidirectional"))
    )
    (net (code "72") (name "unconnected-(U1-(AD3)PA3-Pad75)") (class "Default")
      (node (ref "U1") (pin "75") (pinfunction "(AD3)PA3_75") (pintype "bidirectional"))
    )
    (net (code "73") (name "unconnected-(U1-(ADC0)PF0-Pad97)") (class "Default")
      (node (ref "U1") (pin "97") (pinfunction "(ADC0)PF0_97") (pintype "bidirectional"))
    )
    (net (code "74") (name "unconnected-(U1-(ADC1)PF1-Pad96)") (class "Default")
      (node (ref "U1") (pin "96") (pinfunction "(ADC1)PF1_96") (pintype "bidirectional"))
    )
    (net (code "75") (name "unconnected-(U1-(ADC2)PF2-Pad95)") (class "Default")
      (node (ref "U1") (pin "95") (pinfunction "(ADC2)PF2_95") (pintype "bidirectional"))
    )
    (net (code "76") (name "unconnected-(U1-(ADC3)PF3-Pad94)") (class "Default")
      (node (ref "U1") (pin "94") (pinfunction "(ADC3)PF3_94") (pintype "bidirectional"))
    )
    (net (code "77") (name "unconnected-(U1-(ADC4{slash}TCK)PF4-Pad93)") (class "Default")
      (node (ref "U1") (pin "93") (pinfunction "(ADC4/TCK)PF4_93") (pintype "bidirectional"))
    )
    (net (code "78") (name "unconnected-(U1-(ADC5{slash}TMS)PF5-Pad92)") (class "Default")
      (node (ref "U1") (pin "92") (pinfunction "(ADC5/TMS)PF5_92") (pintype "bidirectional"))
    )
    (net (code "79") (name "unconnected-(U1-(ADC6{slash}TDO)PF6-Pad91)") (class "Default")
      (node (ref "U1") (pin "91") (pinfunction "(ADC6/TDO)PF6_91") (pintype "bidirectional"))
    )
    (net (code "80") (name "unconnected-(U1-(ADC7{slash}TDI)PF7-Pad90)") (class "Default")
      (node (ref "U1") (pin "90") (pinfunction "(ADC7/TDI)PF7_90") (pintype "bidirectional"))
    )
    (net (code "81") (name "unconnected-(U1-(ALE)PG2-Pad70)") (class "Default")
      (node (ref "U1") (pin "70") (pinfunction "(ALE)PG2_70") (pintype "bidirectional"))
    )
    (net (code "82") (name "unconnected-(U1-(CLKO{slash}ICP3{slash}INT7)PE7-Pad9)") (class "Default")
      (node (ref "U1") (pin "9") (pinfunction "(CLKO/ICP3/INT7)PE7_9") (pintype "bidirectional"))
    )
    (net (code "83") (name "unconnected-(U1-(ICP1)PD4-Pad47)") (class "Default")
      (node (ref "U1") (pin "47") (pinfunction "(ICP1)PD4_47") (pintype "bidirectional"))
    )
    (net (code "84") (name "unconnected-(U1-(OC0A{slash}OC1C{slash}PCINT7)PB7-Pad26)") (class "Default")
      (node (ref "U1") (pin "26") (pinfunction "(OC0A/OC1C/PCINT7)PB7_26") (pintype "bidirectional"))
    )
    (net (code "85") (name "unconnected-(U1-(OC0B)PG5-Pad1)") (class "Default")
      (node (ref "U1") (pin "1") (pinfunction "(OC0B)PG5_1") (pintype "bidirectional"))
    )
    (net (code "86") (name "unconnected-(U1-(OC1A{slash}PCINT5)PB5-Pad24)") (class "Default")
      (node (ref "U1") (pin "24") (pinfunction "(OC1A/PCINT5)PB5_24") (pintype "bidirectional"))
    )
    (net (code "87") (name "unconnected-(U1-(OC1B{slash}PCINT6)PB6-Pad25)") (class "Default")
      (node (ref "U1") (pin "25") (pinfunction "(OC1B/PCINT6)PB6_25") (pintype "bidirectional"))
    )
    (net (code "88") (name "unconnected-(U1-(OC2A{slash}PCINT4)PB4-Pad23)") (class "Default")
      (node (ref "U1") (pin "23") (pinfunction "(OC2A/PCINT4)PB4_23") (pintype "bidirectional"))
    )
    (net (code "89") (name "unconnected-(U1-(OC3B{slash}INT4)PE4-Pad6)") (class "Default")
      (node (ref "U1") (pin "6") (pinfunction "(OC3B/INT4)PE4_6") (pintype "bidirectional"))
    )
    (net (code "90") (name "unconnected-(U1-(OC3C{slash}INT5)PE5-Pad7)") (class "Default")
      (node (ref "U1") (pin "7") (pinfunction "(OC3C/INT5)PE5_7") (pintype "bidirectional"))
    )
    (net (code "91") (name "unconnected-(U1-(RD)PG1-Pad52)") (class "Default")
      (node (ref "U1") (pin "52") (pinfunction "(RD)PG1_52") (pintype "bidirectional"))
    )
    (net (code "92") (name "unconnected-(U1-(SS{slash}PCINT0)PB0-Pad19)") (class "Default")
      (node (ref "U1") (pin "19") (pinfunction "(SS/PCINT0)PB0_19") (pintype "bidirectional"))
    )
    (net (code "93") (name "unconnected-(U1-(T0)PD7-Pad50)") (class "Default")
      (node (ref "U1") (pin "50") (pinfunction "(T0)PD7_50") (pintype "bidirectional"))
    )
    (net (code "94") (name "unconnected-(U1-(T1)PD6-Pad49)") (class "Default")
      (node (ref "U1") (pin "49") (pinfunction "(T1)PD6_49") (pintype "bidirectional"))
    )
    (net (code "95") (name "unconnected-(U1-(T3{slash}INT6)PE6-Pad8)") (class "Default")
      (node (ref "U1") (pin "8") (pinfunction "(T3/INT6)PE6_8") (pintype "bidirectional"))
    )
    (net (code "96") (name "unconnected-(U1-(TOSC1)PG4-Pad29)") (class "Default")
      (node (ref "U1") (pin "29") (pinfunction "(TOSC1)PG4_29") (pintype "bidirectional"))
    )
    (net (code "97") (name "unconnected-(U1-(TOSC2)PG3-Pad28)") (class "Default")
      (node (ref "U1") (pin "28") (pinfunction "(TOSC2)PG3_28") (pintype "bidirectional"))
    )
    (net (code "98") (name "unconnected-(U1-(WR)PG0-Pad51)") (class "Default")
      (node (ref "U1") (pin "51") (pinfunction "(WR)PG0_51") (pintype "bidirectional"))
    )
    (net (code "99") (name "unconnected-(U1-(XCK1)PD5-Pad48)") (class "Default")
      (node (ref "U1") (pin "48") (pinfunction "(XCK1)PD5_48") (pintype "bidirectional"))
    )
    (net (code "100") (name "unconnected-(U1-PH0(RXD2)-Pad12)") (class "Default")
      (node (ref "U1") (pin "12") (pinfunction "PH0(RXD2)_12") (pintype "bidirectional"))
    )
    (net (code "101") (name "unconnected-(U1-PH1(TXD2)-Pad13)") (class "Default")
      (node (ref "U1") (pin "13") (pinfunction "PH1(TXD2)_13") (pintype "bidirectional"))
    )
    (net (code "102") (name "unconnected-(U1-PH2(XCK2)-Pad14)") (class "Default")
      (node (ref "U1") (pin "14") (pinfunction "PH2(XCK2)_14") (pintype "bidirectional"))
    )
    (net (code "103") (name "unconnected-(U1-PH3(OC4A)-Pad15)") (class "Default")
      (node (ref "U1") (pin "15") (pinfunction "PH3(OC4A)_15") (pintype "bidirectional"))
    )
    (net (code "104") (name "unconnected-(U1-PH4(OC4B)-Pad16)") (class "Default")
      (node (ref "U1") (pin "16") (pinfunction "PH4(OC4B)_16") (pintype "bidirectional"))
    )
    (net (code "105") (name "unconnected-(U1-PH5(OC4C)-Pad17)") (class "Default")
      (node (ref "U1") (pin "17") (pinfunction "PH5(OC4C)_17") (pintype "bidirectional"))
    )
    (net (code "106") (name "unconnected-(U1-PH6(OC2B)-Pad18)") (class "Default")
      (node (ref "U1") (pin "18") (pinfunction "PH6(OC2B)_18") (pintype "bidirectional"))
    )
    (net (code "107") (name "unconnected-(U1-PH7(T4)-Pad27)") (class "Default")
      (node (ref "U1") (pin "27") (pinfunction "PH7(T4)_27") (pintype "bidirectional"))
    )
    (net (code "108") (name "unconnected-(U1-PJ2(XCK3{slash}PCINT11)-Pad65)") (class "Default")
      (node (ref "U1") (pin "65") (pinfunction "PJ2(XCK3/PCINT11)_65") (pintype "bidirectional"))
    )
    (net (code "109") (name "unconnected-(U1-PJ3(PCINT12)-Pad66)") (class "Default")
      (node (ref "U1") (pin "66") (pinfunction "PJ3(PCINT12)_66") (pintype "bidirectional"))
    )
    (net (code "110") (name "unconnected-(U1-PJ4(PCINT13)-Pad67)") (class "Default")
      (node (ref "U1") (pin "67") (pinfunction "PJ4(PCINT13)_67") (pintype "bidirectional"))
    )
    (net (code "111") (name "unconnected-(U1-PJ5(PCINT14)-Pad68)") (class "Default")
      (node (ref "U1") (pin "68") (pinfunction "PJ5(PCINT14)_68") (pintype "bidirectional"))
    )
    (net (code "112") (name "unconnected-(U1-PJ6(PCINT15)-Pad69)") (class "Default")
      (node (ref "U1") (pin "69") (pinfunction "PJ6(PCINT15)_69") (pintype "bidirectional"))
    )
    (net (code "113") (name "unconnected-(U1-PJ7-Pad79)") (class "Default")
      (node (ref "U1") (pin "79") (pinfunction "PJ7_79") (pintype "bidirectional"))
    )
    (net (code "114") (name "unconnected-(U1-PK0(ADC8{slash}PCINT16)-Pad89)") (class "Default")
      (node (ref "U1") (pin "89") (pinfunction "PK0(ADC8/PCINT16)_89") (pintype "bidirectional"))
    )
    (net (code "115") (name "unconnected-(U1-PK1(ADC9{slash}PCINT17)-Pad88)") (class "Default")
      (node (ref "U1") (pin "88") (pinfunction "PK1(ADC9/PCINT17)_88") (pintype "bidirectional"))
    )
    (net (code "116") (name "unconnected-(U1-PK2(ADC10{slash}PCINT18)-Pad87)") (class "Default")
      (node (ref "U1") (pin "87") (pinfunction "PK2(ADC10/PCINT18)_87") (pintype "bidirectional"))
    )
    (net (code "117") (name "unconnected-(U1-PK3(ADC11{slash}PCINT19)-Pad86)") (class "Default")
      (node (ref "U1") (pin "86") (pinfunction "PK3(ADC11/PCINT19)_86") (pintype "bidirectional"))
    )
    (net (code "118") (name "unconnected-(U1-PL3(OC5A)-Pad38)") (class "Default")
      (node (ref "U1") (pin "38") (pinfunction "PL3(OC5A)_38") (pintype "bidirectional"))
    )
    (net (code "119") (name "unconnected-(U1-PL4(OC5B)-Pad39)") (class "Default")
      (node (ref "U1") (pin "39") (pinfunction "PL4(OC5B)_39") (pintype "bidirectional"))
    )
    (net (code "120") (name "unconnected-(U1-PL5(OC5C)-Pad40)") (class "Default")
      (node (ref "U1") (pin "40") (pinfunction "PL5(OC5C)_40") (pintype "bidirectional"))
    )
    (net (code "121") (name "unconnected-(U1-PL6-Pad41)") (class "Default")
      (node (ref "U1") (pin "41") (pinfunction "PL6_41") (pintype "bidirectional"))
    )
    (net (code "122") (name "unconnected-(U1-PL7-Pad42)") (class "Default")
      (node (ref "U1") (pin "42") (pinfunction "PL7_42") (pintype "bidirectional"))
    )
    (net (code "123") (name "unconnected-(U2-3V3OUT-Pad17)") (class "Default")
      (node (ref "U2") (pin "17") (pinfunction "3V3OUT_17") (pintype "output"))
    )
    (net (code "124") (name "unconnected-(U2-DCD-Pad10)") (class "Default")
      (node (ref "U2") (pin "10") (pinfunction "DCD_10") (pintype "input"))
    )
    (net (code "125") (name "unconnected-(U2-DSR-Pad9)") (class "Default")
      (node (ref "U2") (pin "9") (pinfunction "DSR_9") (pintype "input"))
    )
    (net (code "126") (name "unconnected-(U2-OSCI-Pad27)") (class "Default")
      (node (ref "U2") (pin "27") (pinfunction "OSCI_27") (pintype "input"))
    )
    (net (code "127") (name "unconnected-(U2-OSCO-Pad28)") (class "Default")
      (node (ref "U2") (pin "28") (pinfunction "OSCO_28") (pintype "output"))
    )
    (net (code "128") (name "unconnected-(U2-PWREN-Pad14)") (class "Default")
      (node (ref "U2") (pin "14") (pinfunction "PWREN_14") (pintype "input"))
    )
    (net (code "129") (name "unconnected-(U2-RI-Pad6)") (class "Default")
      (node (ref "U2") (pin "6") (pinfunction "RI_6") (pintype "input"))
    )
    (net (code "130") (name "unconnected-(U2-RTS-Pad3)") (class "Default")
      (node (ref "U2") (pin "3") (pinfunction "RTS_3") (pintype "output"))
    )
    (net (code "131") (name "unconnected-(U2-SLEEP-Pad12)") (class "Default")
      (node (ref "U2") (pin "12") (pinfunction "SLEEP_12") (pintype "input"))
    )
    (net (code "132") (name "unconnected-(U2-TXDEN-Pad13)") (class "Default")
      (node (ref "U2") (pin "13") (pinfunction "TXDEN_13") (pintype "input"))
    )
    (net (code "133") (name "unconnected-(U3-PB1-Pad6)") (class "Default")
      (node (ref "U3") (pin "6") (pinfunction "PB1_6") (pintype "bidirectional"))
    )
    (net (code "134") (name "unconnected-(U3-PB3-Pad2)") (class "Default")
      (node (ref "U3") (pin "2") (pinfunction "PB3_2") (pintype "bidirectional"))
    )
    (net (code "135") (name "unconnected-(U3-PB5-Pad1)") (class "Default")
      (node (ref "U3") (pin "1") (pinfunction "PB5_1") (pintype "bidirectional"))
    )
    (net (code "136") (name "unconnected-(U4-PB1-Pad6)") (class "Default")
      (node (ref "U4") (pin "6") (pinfunction "PB1_6") (pintype "bidirectional"))
    )
    (net (code "137") (name "unconnected-(U4-PB3-Pad2)") (class "Default")
      (node (ref "U4") (pin "2") (pinfunction "PB3_2") (pintype "bidirectional"))
    )
    (net (code "138") (name "unconnected-(U4-PB5-Pad1)") (class "Default")
      (node (ref "U4") (pin "1") (pinfunction "PB5_1") (pintype "bidirectional"))
    )
    (net (code "139") (name "unconnected-(U6-~{Y}-Pad3)") (class "Default")
      (node (ref "U6") (pin "3") (pinfunction "~{Y}_3") (pintype "output"))
    )
    (net (code "140") (name "unconnected-(U7-~{Y}-Pad3)") (class "Default")
      (node (ref "U7") (pin "3") (pinfunction "~{Y}_3") (pintype "output"))
    )
    (net (code "141") (name "unconnected-(U8-~{Y}-Pad3)") (class "Default")
      (node (ref "U8") (pin "3") (pinfunction "~{Y}_3") (pintype "output"))
    )
    (net (code "142") (name "unconnected-(U9-~{Y}-Pad3)") (class "Default")
      (node (ref "U9") (pin "3") (pinfunction "~{Y}_3") (pintype "output"))
    )
    (net (code "143") (name "unconnected-(X4D-KL-Pad3)") (class "Default")
      (node (ref "X4") (pin "3") (pinfunction "KL_3") (pintype "passive"))
    )
    (net (code "144") (name "unconnected-(X4E-KL-Pad4)") (class "Default")
      (node (ref "X4") (pin "4") (pinfunction "KL_4") (pintype "passive"))
    )
    (net (code "145") (name "unconnected-(X5D-KL-Pad3)") (class "Default")
      (node (ref "X5") (pin "3") (pinfunction "KL_3") (pintype "passive"))
    )
    (net (code "146") (name "unconnected-(X5E-KL-Pad4)") (class "Default")
      (node (ref "X5") (pin "4") (pinfunction "KL_4") (pintype "passive"))
    )
  )
)
